# SGOv2.net
KiCad netlist of a schematic drawn in EAGLE
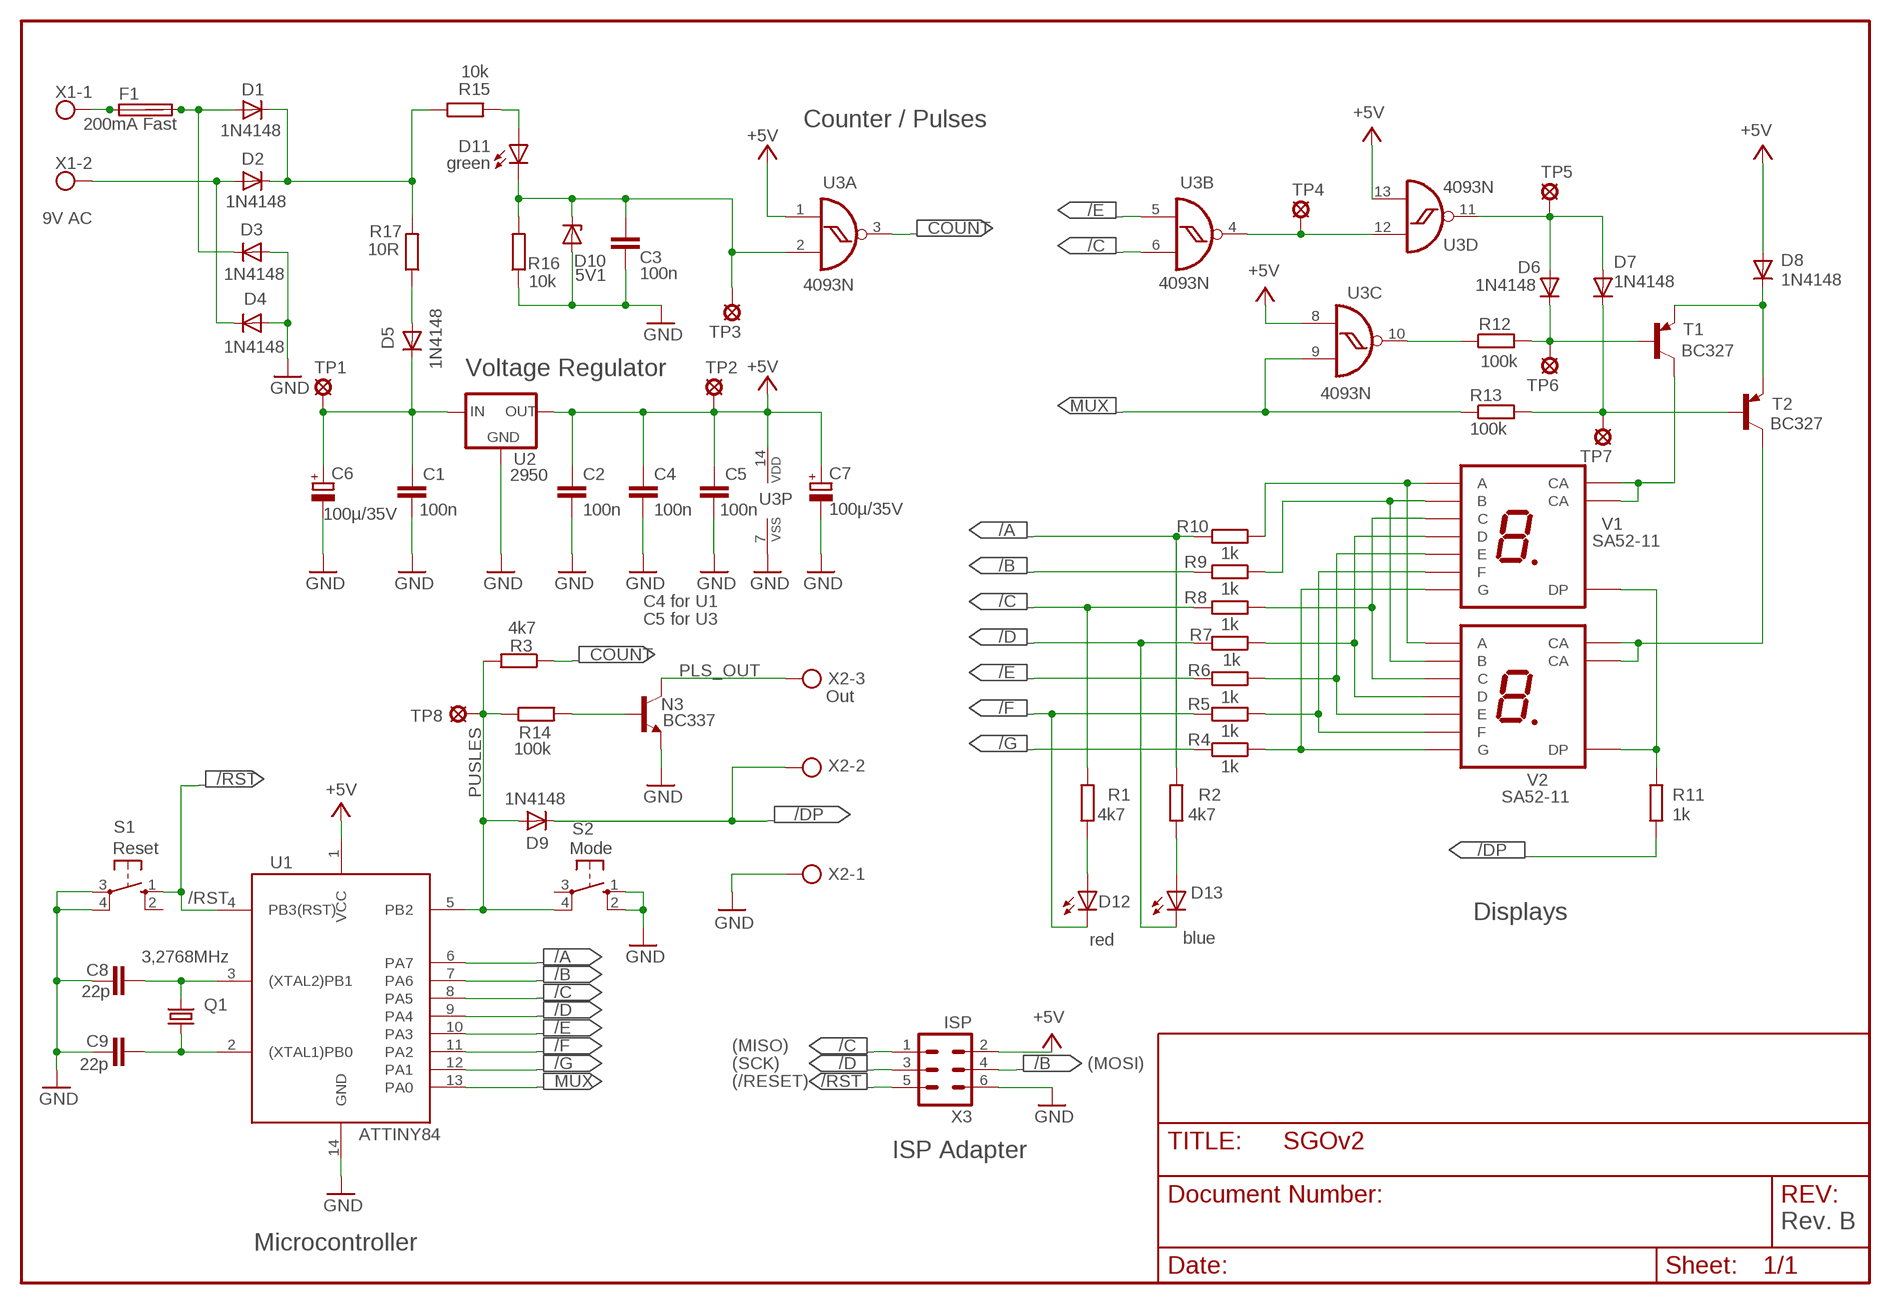
[diagram p0: schematic, sheet 1]

(export (version "E")
  (design (tool "Eeschema 10.0.6"))
  (components
    (comp (ref "C1")
      (value "100n")
      (footprint "eagle-import:C025-024X044")
      (libsource (lib "eagle-import") (part "C-EU025-024X044"))
    )
    (comp (ref "C2")
      (value "100n")
      (footprint "eagle-import:C025-024X044")
      (libsource (lib "eagle-import") (part "C-EU025-024X044"))
    )
    (comp (ref "C3")
      (value "100n")
      (footprint "eagle-import:C025-024X044")
      (libsource (lib "eagle-import") (part "C-EU025-024X044"))
    )
    (comp (ref "C4")
      (value "100n")
      (footprint "eagle-import:C025-024X044")
      (libsource (lib "eagle-import") (part "C-EU025-024X044"))
    )
    (comp (ref "C5")
      (value "100n")
      (footprint "eagle-import:C025-024X044")
      (libsource (lib "eagle-import") (part "C-EU025-024X044"))
    )
    (comp (ref "C6")
      (value "100µ/35V")
      (footprint "eagle-import:E2,5-7")
      (libsource (lib "eagle-import") (part "CPOL-EUE2.5-7"))
    )
    (comp (ref "C7")
      (value "100µ/35V")
      (footprint "eagle-import:E2,5-7")
      (libsource (lib "eagle-import") (part "CPOL-EUE2.5-7"))
    )
    (comp (ref "C8")
      (value "22p")
      (footprint "eagle-import:C025-024X044")
      (libsource (lib "eagle-import") (part "C-EU025-024X044"))
    )
    (comp (ref "C9")
      (value "22p")
      (footprint "eagle-import:C025-024X044")
      (libsource (lib "eagle-import") (part "C-EU025-024X044"))
    )
    (comp (ref "D1")
      (value "1N4148")
      (footprint "eagle-import:DO35-10")
      (libsource (lib "eagle-import") (part "1N4148"))
    )
    (comp (ref "D2")
      (value "1N4148")
      (footprint "eagle-import:DO35-10")
      (libsource (lib "eagle-import") (part "1N4148"))
    )
    (comp (ref "D3")
      (value "1N4148")
      (footprint "eagle-import:DO35-10")
      (libsource (lib "eagle-import") (part "1N4148"))
    )
    (comp (ref "D4")
      (value "1N4148")
      (footprint "eagle-import:DO35-10")
      (libsource (lib "eagle-import") (part "1N4148"))
    )
    (comp (ref "D5")
      (value "1N4148")
      (footprint "eagle-import:DO35-10")
      (libsource (lib "eagle-import") (part "1N4148"))
    )
    (comp (ref "D6")
      (value "1N4148")
      (footprint "eagle-import:DO35-10")
      (libsource (lib "eagle-import") (part "1N4148"))
    )
    (comp (ref "D7")
      (value "1N4148")
      (footprint "eagle-import:DO35-10")
      (libsource (lib "eagle-import") (part "1N4148"))
    )
    (comp (ref "D8")
      (value "1N4148")
      (footprint "eagle-import:DO35-10")
      (libsource (lib "eagle-import") (part "1N4148"))
    )
    (comp (ref "D9")
      (value "1N4148")
      (footprint "eagle-import:DO35-10")
      (libsource (lib "eagle-import") (part "1N4148"))
    )
    (comp (ref "D10")
      (value "5V1")
      (footprint "eagle-import:DO35Z10")
      (libsource (lib "eagle-import") (part "ZPD"))
    )
    (comp (ref "D11")
      (value "green")
      (footprint "eagle-import:LED3MM")
      (libsource (lib "eagle-import") (part "LED3MM"))
    )
    (comp (ref "D12")
      (value "red")
      (footprint "eagle-import:LED3MM")
      (libsource (lib "eagle-import") (part "LED3MM"))
    )
    (comp (ref "D13")
      (value "blue")
      (footprint "eagle-import:LED3MM")
      (libsource (lib "eagle-import") (part "LED3MM"))
    )
    (comp (ref "F1")
      (value "200mA Fast")
      (footprint "eagle-import:SHK20Q")
      (libsource (lib "eagle-import") (part "SHK20Q"))
    )
    (comp (ref "F2")
      (value "FUSESH22,5")
      (footprint "eagle-import:SH22,5")
      (libsource (lib "eagle-import") (part "FUSESH22,5"))
    )
    (comp (ref "N3")
      (value "BC337")
      (footprint "eagle-import:TO92")
      (libsource (lib "eagle-import") (part "BC337-40"))
    )
    (comp (ref "Q1")
      (value "3,2768MHz")
      (footprint "eagle-import:HC49_S")
      (libsource (lib "eagle-import") (part "CRYSTALHC49S"))
    )
    (comp (ref "R1")
      (value "4k7")
      (footprint "eagle-import:0207_10")
      (libsource (lib "eagle-import") (part "R-EU_0207/10"))
    )
    (comp (ref "R2")
      (value "4k7")
      (footprint "eagle-import:0207_10")
      (libsource (lib "eagle-import") (part "R-EU_0207/10"))
    )
    (comp (ref "R3")
      (value "4k7")
      (footprint "eagle-import:0207_10")
      (libsource (lib "eagle-import") (part "R-EU_0207/10"))
    )
    (comp (ref "R4")
      (value "1k")
      (footprint "eagle-import:0207_10")
      (libsource (lib "eagle-import") (part "R-EU_0207/10"))
    )
    (comp (ref "R5")
      (value "1k")
      (footprint "eagle-import:0207_10")
      (libsource (lib "eagle-import") (part "R-EU_0207/10"))
    )
    (comp (ref "R6")
      (value "1k")
      (footprint "eagle-import:0207_10")
      (libsource (lib "eagle-import") (part "R-EU_0207/10"))
    )
    (comp (ref "R7")
      (value "1k")
      (footprint "eagle-import:0207_10")
      (libsource (lib "eagle-import") (part "R-EU_0207/10"))
    )
    (comp (ref "R8")
      (value "1k")
      (footprint "eagle-import:0207_10")
      (libsource (lib "eagle-import") (part "R-EU_0207/10"))
    )
    (comp (ref "R9")
      (value "1k")
      (footprint "eagle-import:0207_10")
      (libsource (lib "eagle-import") (part "R-EU_0207/10"))
    )
    (comp (ref "R10")
      (value "1k")
      (footprint "eagle-import:0207_10")
      (libsource (lib "eagle-import") (part "R-EU_0207/10"))
    )
    (comp (ref "R11")
      (value "1k")
      (footprint "eagle-import:0207_10")
      (libsource (lib "eagle-import") (part "R-EU_0207/10"))
    )
    (comp (ref "R12")
      (value "100k")
      (footprint "eagle-import:0207_10")
      (libsource (lib "eagle-import") (part "R-EU_0207/10"))
    )
    (comp (ref "R13")
      (value "100k")
      (footprint "eagle-import:0207_10")
      (libsource (lib "eagle-import") (part "R-EU_0207/10"))
    )
    (comp (ref "R14")
      (value "100k")
      (footprint "eagle-import:0207_10")
      (libsource (lib "eagle-import") (part "R-EU_0207/10"))
    )
    (comp (ref "R15")
      (value "10k")
      (footprint "eagle-import:0207_10")
      (libsource (lib "eagle-import") (part "R-EU_0207/10"))
    )
    (comp (ref "R16")
      (value "10k")
      (footprint "eagle-import:0207_10")
      (libsource (lib "eagle-import") (part "R-EU_0207/10"))
    )
    (comp (ref "R17")
      (value "10R")
      (footprint "eagle-import:0207_10")
      (libsource (lib "eagle-import") (part "R-EU_0207/10"))
    )
    (comp (ref "S1")
      (value "Reset")
      (footprint "eagle-import:B3F-10XX")
      (libsource (lib "eagle-import") (part "10-XX"))
    )
    (comp (ref "S2")
      (value "Mode")
      (footprint "eagle-import:B3F-10XX")
      (libsource (lib "eagle-import") (part "10-XX"))
    )
    (comp (ref "T1")
      (value "BC327")
      (footprint "eagle-import:TO92")
      (libsource (lib "eagle-import") (part "BC327"))
    )
    (comp (ref "T2")
      (value "BC327")
      (footprint "eagle-import:TO92")
      (libsource (lib "eagle-import") (part "BC327"))
    )
    (comp (ref "TP1")
      (value "V+")
      (footprint "eagle-import:LSP10")
      (libsource (lib "eagle-import") (part "LSP10"))
    )
    (comp (ref "TP2")
      (value "+5V")
      (footprint "eagle-import:LSP10")
      (libsource (lib "eagle-import") (part "LSP10"))
    )
    (comp (ref "TP3")
      (value "C-V5")
      (footprint "eagle-import:LSP10")
      (libsource (lib "eagle-import") (part "LSP10"))
    )
    (comp (ref "TP4")
      (value "/EC")
      (footprint "eagle-import:LSP10")
      (libsource (lib "eagle-import") (part "LSP10"))
    )
    (comp (ref "TP5")
      (value "EC")
      (footprint "eagle-import:LSP10")
      (libsource (lib "eagle-import") (part "LSP10"))
    )
    (comp (ref "TP6")
      (value "B-N1")
      (footprint "eagle-import:LSP10")
      (libsource (lib "eagle-import") (part "LSP10"))
    )
    (comp (ref "TP7")
      (value "B-N2")
      (footprint "eagle-import:LSP10")
      (libsource (lib "eagle-import") (part "LSP10"))
    )
    (comp (ref "TP8")
      (value "PLS")
      (footprint "eagle-import:LSP10")
      (libsource (lib "eagle-import") (part "LSP10"))
    )
    (comp (ref "U1")
      (value "ATTINY84")
      (footprint "eagle-import:DIL14")
      (libsource (lib "eagle-import") (part "ATTINY24/44/84-PU"))
    )
    (comp (ref "U2")
      (value "2950")
      (footprint "eagle-import:TO92")
      (libsource (lib "eagle-import") (part "78LXX"))
    )
    (comp (ref "U3")
      (value "4093N")
      (footprint "eagle-import:DIL14")
      (libsource (lib "eagle-import") (part "4093N"))
    )
    (comp (ref "V1")
      (value "SA52-11")
      (footprint "eagle-import:KB-SX52-11")
      (libsource (lib "eagle-import") (part "SA52-11"))
    )
    (comp (ref "V2")
      (value "SA52-11")
      (footprint "eagle-import:KB-SX52-11")
      (libsource (lib "eagle-import") (part "SA52-11"))
    )
    (comp (ref "X1")
      (value "9V AC")
      (footprint "eagle-import:W237-102")
      (libsource (lib "eagle-import") (part "W237-102"))
    )
    (comp (ref "X2")
      (value "Out")
      (footprint "eagle-import:W237-103")
      (libsource (lib "eagle-import") (part "W237-103"))
    )
    (comp (ref "X3")
      (value "ISP")
      (footprint "eagle-import:ML6")
      (libsource (lib "eagle-import") (part "ML6"))
    )
  )
  (nets
    (net (code "1") (name "+5V") (class "Default")
      (node (ref "C2") (pin "1") (pinfunction "1_1") (pintype "passive"))
      (node (ref "C4") (pin "1") (pinfunction "1_1") (pintype "passive"))
      (node (ref "C5") (pin "1") (pinfunction "1_1") (pintype "passive"))
      (node (ref "C7") (pin "+") (pinfunction "+_+") (pintype "passive"))
      (node (ref "D8") (pin "A") (pinfunction "A_A") (pintype "passive"))
      (node (ref "TP2") (pin "MP") (pinfunction "MP_MP") (pintype "passive"))
      (node (ref "U1") (pin "1") (pinfunction "VCC_1") (pintype "power_in"))
      (node (ref "U2") (pin "1") (pinfunction "OUT_1") (pintype "passive"))
      (node (ref "U3") (pin "1") (pinfunction "I0_1") (pintype "input"))
      (node (ref "U3") (pin "13") (pinfunction "I1_13") (pintype "input"))
      (node (ref "U3") (pin "14") (pinfunction "VDD_14") (pintype "power_in"))
      (node (ref "U3") (pin "8") (pinfunction "I0_8") (pintype "input"))
      (node (ref "X3") (pin "2") (pinfunction "2_2") (pintype "passive"))
    )
    (net (code "2") (name "/COUNT") (class "Default")
      (node (ref "R3") (pin "1") (pinfunction "1_1") (pintype "passive"))
      (node (ref "U3") (pin "3") (pinfunction "O_3") (pintype "output"))
    )
    (net (code "3") (name "/MUX") (class "Default")
      (node (ref "R13") (pin "1") (pinfunction "1_1") (pintype "passive"))
      (node (ref "U1") (pin "13") (pinfunction "PA0_13") (pintype "bidirectional"))
      (node (ref "U3") (pin "9") (pinfunction "I1_9") (pintype "input"))
    )
    (net (code "4") (name "/PLS_OUT") (class "Default")
      (node (ref "N3") (pin "1") (pinfunction "C_1") (pintype "passive"))
      (node (ref "X2") (pin "3") (pinfunction "KL_3") (pintype "passive"))
    )
    (net (code "5") (name "/PUSLES") (class "Default")
      (node (ref "D9") (pin "A") (pinfunction "A_A") (pintype "passive"))
      (node (ref "R14") (pin "1") (pinfunction "1_1") (pintype "passive"))
      (node (ref "R3") (pin "2") (pinfunction "2_2") (pintype "passive"))
      (node (ref "S2") (pin "4") (pinfunction "P1_4") (pintype "passive"))
      (node (ref "TP8") (pin "MP") (pinfunction "MP_MP") (pintype "passive"))
      (node (ref "U1") (pin "5") (pinfunction "PB2_5") (pintype "bidirectional"))
    )
    (net (code "6") (name "/{slash}A") (class "Default")
      (node (ref "R10") (pin "2") (pinfunction "2_2") (pintype "passive"))
      (node (ref "R2") (pin "2") (pinfunction "2_2") (pintype "passive"))
      (node (ref "U1") (pin "6") (pinfunction "PA7_6") (pintype "bidirectional"))
    )
    (net (code "7") (name "/{slash}B") (class "Default")
      (node (ref "R9") (pin "2") (pinfunction "2_2") (pintype "passive"))
      (node (ref "U1") (pin "7") (pinfunction "PA6_7") (pintype "bidirectional"))
      (node (ref "X3") (pin "4") (pinfunction "4_4") (pintype "passive"))
    )
    (net (code "8") (name "/{slash}C") (class "Default")
      (node (ref "R1") (pin "2") (pinfunction "2_2") (pintype "passive"))
      (node (ref "R8") (pin "2") (pinfunction "2_2") (pintype "passive"))
      (node (ref "U1") (pin "8") (pinfunction "PA5_8") (pintype "bidirectional"))
      (node (ref "U3") (pin "6") (pinfunction "I1_6") (pintype "input"))
      (node (ref "X3") (pin "1") (pinfunction "1_1") (pintype "passive"))
    )
    (net (code "9") (name "/{slash}D") (class "Default")
      (node (ref "D13") (pin "K") (pinfunction "C_K") (pintype "passive"))
      (node (ref "R7") (pin "2") (pinfunction "2_2") (pintype "passive"))
      (node (ref "U1") (pin "9") (pinfunction "PA4_9") (pintype "bidirectional"))
      (node (ref "X3") (pin "3") (pinfunction "3_3") (pintype "passive"))
    )
    (net (code "10") (name "/{slash}DP") (class "Default")
      (node (ref "D9") (pin "C") (pinfunction "C_C") (pintype "passive"))
      (node (ref "R11") (pin "1") (pinfunction "1_1") (pintype "passive"))
      (node (ref "X2") (pin "2") (pinfunction "KL_2") (pintype "passive"))
    )
    (net (code "11") (name "/{slash}E") (class "Default")
      (node (ref "R6") (pin "2") (pinfunction "2_2") (pintype "passive"))
      (node (ref "U1") (pin "10") (pinfunction "PA3_10") (pintype "bidirectional"))
      (node (ref "U3") (pin "5") (pinfunction "I0_5") (pintype "input"))
    )
    (net (code "12") (name "/{slash}F") (class "Default")
      (node (ref "D12") (pin "K") (pinfunction "C_K") (pintype "passive"))
      (node (ref "R5") (pin "2") (pinfunction "2_2") (pintype "passive"))
      (node (ref "U1") (pin "11") (pinfunction "PA2_11") (pintype "bidirectional"))
    )
    (net (code "13") (name "/{slash}G") (class "Default")
      (node (ref "R4") (pin "2") (pinfunction "2_2") (pintype "passive"))
      (node (ref "U1") (pin "12") (pinfunction "PA1_12") (pintype "bidirectional"))
    )
    (net (code "14") (name "/{slash}RST") (class "Default")
      (node (ref "S1") (pin "1") (pinfunction "S_1") (pintype "passive"))
      (node (ref "U1") (pin "4") (pinfunction "PB3(RST)_4") (pintype "bidirectional"))
      (node (ref "X3") (pin "5") (pinfunction "5_5") (pintype "passive"))
    )
    (net (code "15") (name "GND") (class "Default")
      (node (ref "C1") (pin "2") (pinfunction "2_2") (pintype "passive"))
      (node (ref "C2") (pin "2") (pinfunction "2_2") (pintype "passive"))
      (node (ref "C3") (pin "2") (pinfunction "2_2") (pintype "passive"))
      (node (ref "C4") (pin "2") (pinfunction "2_2") (pintype "passive"))
      (node (ref "C5") (pin "2") (pinfunction "2_2") (pintype "passive"))
      (node (ref "C6") (pin "-") (pinfunction "-_-") (pintype "passive"))
      (node (ref "C7") (pin "-") (pinfunction "-_-") (pintype "passive"))
      (node (ref "C8") (pin "1") (pinfunction "1_1") (pintype "passive"))
      (node (ref "C9") (pin "1") (pinfunction "1_1") (pintype "passive"))
      (node (ref "D10") (pin "A") (pinfunction "A_A") (pintype "passive"))
      (node (ref "D3") (pin "A") (pinfunction "A_A") (pintype "passive"))
      (node (ref "D4") (pin "A") (pinfunction "A_A") (pintype "passive"))
      (node (ref "N3") (pin "3") (pinfunction "E_3") (pintype "passive"))
      (node (ref "R16") (pin "1") (pinfunction "1_1") (pintype "passive"))
      (node (ref "S1") (pin "3") (pinfunction "P_3") (pintype "passive"))
      (node (ref "S1") (pin "4") (pinfunction "P1_4") (pintype "passive"))
      (node (ref "S2") (pin "1") (pinfunction "S_1") (pintype "passive"))
      (node (ref "S2") (pin "2") (pinfunction "S1_2") (pintype "passive"))
      (node (ref "U1") (pin "14") (pinfunction "GND_14") (pintype "power_in"))
      (node (ref "U2") (pin "2") (pinfunction "GND_2") (pintype "input"))
      (node (ref "U3") (pin "7") (pinfunction "VSS_7") (pintype "power_in"))
      (node (ref "X2") (pin "1") (pinfunction "KL_1") (pintype "passive"))
      (node (ref "X3") (pin "6") (pinfunction "6_6") (pintype "passive"))
    )
    (net (code "16") (name "Net-(D1-PadA)") (class "Default")
      (node (ref "D1") (pin "A") (pinfunction "A_A") (pintype "passive"))
      (node (ref "D3") (pin "C") (pinfunction "C_C") (pintype "passive"))
      (node (ref "F1") (pin "2A") (pinfunction "2A_2A") (pintype "passive"))
      (node (ref "F2") (pin "2") (pinfunction "2_2") (pintype "passive"))
    )
    (net (code "17") (name "Net-(D1-PadC)") (class "Default")
      (node (ref "D1") (pin "C") (pinfunction "C_C") (pintype "passive"))
      (node (ref "D2") (pin "C") (pinfunction "C_C") (pintype "passive"))
      (node (ref "R15") (pin "1") (pinfunction "1_1") (pintype "passive"))
      (node (ref "R17") (pin "2") (pinfunction "2_2") (pintype "passive"))
    )
    (net (code "18") (name "Net-(D5-PadA)") (class "Default")
      (node (ref "D5") (pin "A") (pinfunction "A_A") (pintype "passive"))
      (node (ref "R17") (pin "1") (pinfunction "1_1") (pintype "passive"))
    )
    (net (code "19") (name "Net-(D11-C)") (class "Default")
      (node (ref "C3") (pin "1") (pinfunction "1_1") (pintype "passive"))
      (node (ref "D10") (pin "C") (pinfunction "C_C") (pintype "passive"))
      (node (ref "D11") (pin "K") (pinfunction "C_K") (pintype "passive"))
      (node (ref "R16") (pin "2") (pinfunction "2_2") (pintype "passive"))
      (node (ref "TP3") (pin "MP") (pinfunction "MP_MP") (pintype "passive"))
      (node (ref "U3") (pin "2") (pinfunction "I1_2") (pintype "input"))
    )
    (net (code "20") (name "Net-(D11-PadA)") (class "Default")
      (node (ref "D11") (pin "A") (pinfunction "A_A") (pintype "passive"))
      (node (ref "R15") (pin "2") (pinfunction "2_2") (pintype "passive"))
    )
    (net (code "21") (name "Net-(D12-PadA)") (class "Default")
      (node (ref "D12") (pin "A") (pinfunction "A_A") (pintype "passive"))
      (node (ref "R1") (pin "1") (pinfunction "1_1") (pintype "passive"))
    )
    (net (code "22") (name "Net-(D13-PadA)") (class "Default")
      (node (ref "D13") (pin "A") (pinfunction "A_A") (pintype "passive"))
      (node (ref "R2") (pin "1") (pinfunction "1_1") (pintype "passive"))
    )
    (net (code "23") (name "Net-(N3-B)") (class "Default")
      (node (ref "N3") (pin "2") (pinfunction "B_2") (pintype "passive"))
      (node (ref "R14") (pin "2") (pinfunction "2_2") (pintype "passive"))
    )
    (net (code "24") (name "Net-(T1-B)") (class "Default")
      (node (ref "D6") (pin "C") (pinfunction "C_C") (pintype "passive"))
      (node (ref "R12") (pin "2") (pinfunction "2_2") (pintype "passive"))
      (node (ref "T1") (pin "2") (pinfunction "B_2") (pintype "passive"))
      (node (ref "TP6") (pin "MP") (pinfunction "MP_MP") (pintype "passive"))
    )
    (net (code "25") (name "Net-(T1-C)") (class "Default")
      (node (ref "T1") (pin "1") (pinfunction "C_1") (pintype "passive"))
      (node (ref "V1") (pin "P$3") (pinfunction "CA_P$3") (pintype "passive"))
      (node (ref "V1") (pin "P$8") (pinfunction "CA_P$8") (pintype "passive"))
    )
    (net (code "26") (name "Net-(T1-E)") (class "Default")
      (node (ref "D8") (pin "C") (pinfunction "C_C") (pintype "passive"))
      (node (ref "T1") (pin "3") (pinfunction "E_3") (pintype "passive"))
      (node (ref "T2") (pin "3") (pinfunction "E_3") (pintype "passive"))
    )
    (net (code "27") (name "Net-(T2-B)") (class "Default")
      (node (ref "D7") (pin "C") (pinfunction "C_C") (pintype "passive"))
      (node (ref "R13") (pin "2") (pinfunction "2_2") (pintype "passive"))
      (node (ref "T2") (pin "2") (pinfunction "B_2") (pintype "passive"))
      (node (ref "TP7") (pin "MP") (pinfunction "MP_MP") (pintype "passive"))
    )
    (net (code "28") (name "Net-(T2-C)") (class "Default")
      (node (ref "T2") (pin "1") (pinfunction "C_1") (pintype "passive"))
      (node (ref "V2") (pin "P$3") (pinfunction "CA_P$3") (pintype "passive"))
      (node (ref "V2") (pin "P$8") (pinfunction "CA_P$8") (pintype "passive"))
    )
    (net (code "29") (name "Net-(U1-(XTAL1)PB0)") (class "Default")
      (node (ref "C9") (pin "2") (pinfunction "2_2") (pintype "passive"))
      (node (ref "Q1") (pin "1") (pinfunction "1_1") (pintype "passive"))
      (node (ref "U1") (pin "2") (pinfunction "(XTAL1)PB0_2") (pintype "bidirectional"))
    )
    (net (code "30") (name "Net-(U1-(XTAL2)PB1)") (class "Default")
      (node (ref "C8") (pin "2") (pinfunction "2_2") (pintype "passive"))
      (node (ref "Q1") (pin "2") (pinfunction "2_2") (pintype "passive"))
      (node (ref "U1") (pin "3") (pinfunction "(XTAL2)PB1_3") (pintype "bidirectional"))
    )
    (net (code "31") (name "Net-(U2-IN)") (class "Default")
      (node (ref "C1") (pin "1") (pinfunction "1_1") (pintype "passive"))
      (node (ref "C6") (pin "+") (pinfunction "+_+") (pintype "passive"))
      (node (ref "D5") (pin "C") (pinfunction "C_C") (pintype "passive"))
      (node (ref "TP1") (pin "MP") (pinfunction "MP_MP") (pintype "passive"))
      (node (ref "U2") (pin "3") (pinfunction "IN_3") (pintype "input"))
    )
    (net (code "32") (name "Net-(U3B-O)") (class "Default")
      (node (ref "TP4") (pin "MP") (pinfunction "MP_MP") (pintype "passive"))
      (node (ref "U3") (pin "12") (pinfunction "I0_12") (pintype "input"))
      (node (ref "U3") (pin "4") (pinfunction "O_4") (pintype "output"))
    )
    (net (code "33") (name "Net-(U3C-O)") (class "Default")
      (node (ref "R12") (pin "1") (pinfunction "1_1") (pintype "passive"))
      (node (ref "U3") (pin "10") (pinfunction "O_10") (pintype "output"))
    )
    (net (code "34") (name "Net-(U3D-O)") (class "Default")
      (node (ref "D6") (pin "A") (pinfunction "A_A") (pintype "passive"))
      (node (ref "D7") (pin "A") (pinfunction "A_A") (pintype "passive"))
      (node (ref "TP5") (pin "MP") (pinfunction "MP_MP") (pintype "passive"))
      (node (ref "U3") (pin "11") (pinfunction "O_11") (pintype "output"))
    )
    (net (code "35") (name "Net-(V1-A)") (class "Default")
      (node (ref "R10") (pin "1") (pinfunction "1_1") (pintype "passive"))
      (node (ref "V1") (pin "P$7") (pinfunction "A_P$7") (pintype "passive"))
      (node (ref "V2") (pin "P$7") (pinfunction "A_P$7") (pintype "passive"))
    )
    (net (code "36") (name "Net-(V1-B)") (class "Default")
      (node (ref "R9") (pin "1") (pinfunction "1_1") (pintype "passive"))
      (node (ref "V1") (pin "P$6") (pinfunction "B_P$6") (pintype "passive"))
      (node (ref "V2") (pin "P$6") (pinfunction "B_P$6") (pintype "passive"))
    )
    (net (code "37") (name "Net-(V1-C)") (class "Default")
      (node (ref "R8") (pin "1") (pinfunction "1_1") (pintype "passive"))
      (node (ref "V1") (pin "P$4") (pinfunction "C_P$4") (pintype "passive"))
      (node (ref "V2") (pin "P$4") (pinfunction "C_P$4") (pintype "passive"))
    )
    (net (code "38") (name "Net-(V1-D)") (class "Default")
      (node (ref "R7") (pin "1") (pinfunction "1_1") (pintype "passive"))
      (node (ref "V1") (pin "P$2") (pinfunction "D_P$2") (pintype "passive"))
      (node (ref "V2") (pin "P$2") (pinfunction "D_P$2") (pintype "passive"))
    )
    (net (code "39") (name "Net-(V1-DP)") (class "Default")
      (node (ref "R11") (pin "2") (pinfunction "2_2") (pintype "passive"))
      (node (ref "V1") (pin "P$5") (pinfunction "DP_P$5") (pintype "passive"))
      (node (ref "V2") (pin "P$5") (pinfunction "DP_P$5") (pintype "passive"))
    )
    (net (code "40") (name "Net-(V1-E)") (class "Default")
      (node (ref "R6") (pin "1") (pinfunction "1_1") (pintype "passive"))
      (node (ref "V1") (pin "P$1") (pinfunction "E_P$1") (pintype "passive"))
      (node (ref "V2") (pin "P$1") (pinfunction "E_P$1") (pintype "passive"))
    )
    (net (code "41") (name "Net-(V1-F)") (class "Default")
      (node (ref "R5") (pin "1") (pinfunction "1_1") (pintype "passive"))
      (node (ref "V1") (pin "P$9") (pinfunction "F_P$9") (pintype "passive"))
      (node (ref "V2") (pin "P$9") (pinfunction "F_P$9") (pintype "passive"))
    )
    (net (code "42") (name "Net-(V1-G)") (class "Default")
      (node (ref "R4") (pin "1") (pinfunction "1_1") (pintype "passive"))
      (node (ref "V1") (pin "P$10") (pinfunction "G_P$10") (pintype "passive"))
      (node (ref "V2") (pin "P$10") (pinfunction "G_P$10") (pintype "passive"))
    )
    (net (code "43") (name "Net-(X1A-KL)") (class "Default")
      (node (ref "F1") (pin "1A") (pinfunction "1A_1A") (pintype "passive"))
      (node (ref "F2") (pin "1") (pinfunction "1_1") (pintype "passive"))
      (node (ref "X1") (pin "1") (pinfunction "KL_1") (pintype "passive"))
    )
    (net (code "44") (name "Net-(X1B-KL)") (class "Default")
      (node (ref "D2") (pin "A") (pinfunction "A_A") (pintype "passive"))
      (node (ref "D4") (pin "C") (pinfunction "C_C") (pintype "passive"))
      (node (ref "X1") (pin "2") (pinfunction "KL_2") (pintype "passive"))
    )
    (net (code "45") (name "unconnected-(F1-Pad1B)") (class "Default")
      (node (ref "F1") (pin "1B") (pinfunction "1B_1B") (pintype "passive"))
    )
    (net (code "46") (name "unconnected-(F1-Pad2B)") (class "Default")
      (node (ref "F1") (pin "2B") (pinfunction "2B_2B") (pintype "passive"))
    )
    (net (code "47") (name "unconnected-(S1-S1-Pad2)") (class "Default")
      (node (ref "S1") (pin "2") (pinfunction "S1_2") (pintype "passive"))
    )
    (net (code "48") (name "unconnected-(S2-P-Pad3)") (class "Default")
      (node (ref "S2") (pin "3") (pinfunction "P_3") (pintype "passive"))
    )
  )
)
